# Bean_revE.net
KiCad netlist of a schematic drawn in EAGLE
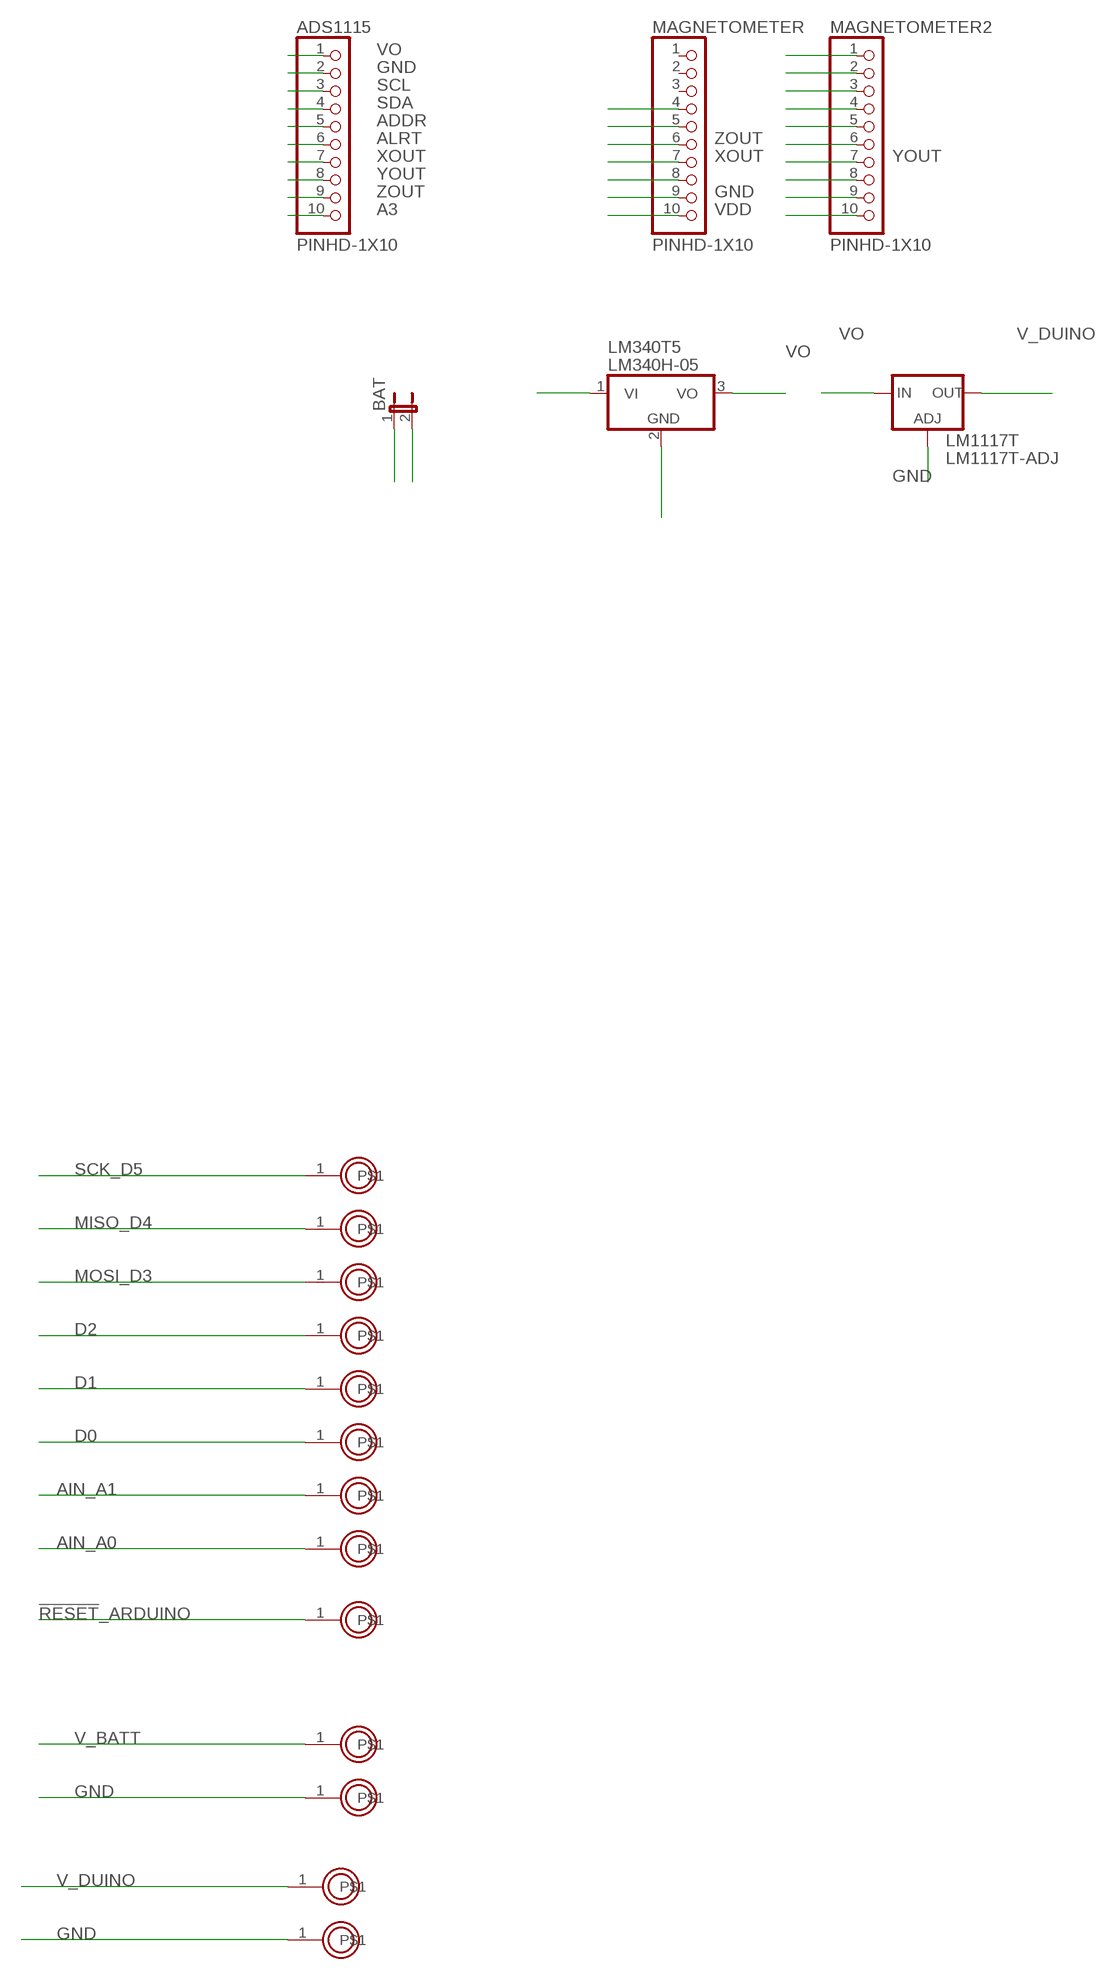
[diagram p0: schematic, sheet 1]

(export (version "E")
  (design (tool "Eeschema 10.0.6"))
  (components
    (comp (ref "ADS1115")
      (value "PINHD-1X10")
      (footprint "eagle-import:1X10-BIG")
      (libsource (lib "eagle-import") (part "PINHD-1X10"))
    )
    (comp (ref "BAT")
      (value "JP1E")
      (footprint "eagle-import:JP1")
      (libsource (lib "eagle-import") (part "JP1E"))
    )
    (comp (ref "LM340T5")
      (value "LM340H-05")
      (footprint "eagle-import:TO220H")
      (libsource (lib "eagle-import") (part "LM340?-H05"))
    )
    (comp (ref "LM1117T")
      (value "LM1117T-ADJ")
      (footprint "eagle-import:TO220")
      (libsource (lib "eagle-import") (part "LM1117T-ADJ"))
    )
    (comp (ref "MAGNETOMETER")
      (value "PINHD-1X10")
      (footprint "eagle-import:1X10-BIG")
      (libsource (lib "eagle-import") (part "PINHD-1X10"))
    )
    (comp (ref "MAGNETOMETER2")
      (value "PINHD-1X10")
      (footprint "eagle-import:1X10-BIG")
      (libsource (lib "eagle-import") (part "PINHD-1X10"))
    )
    (comp (ref "U$1")
      (value "PROTO_POINT")
      (footprint "eagle-import:1X01")
      (libsource (lib "eagle-import") (part "PROTO_POINT"))
    )
    (comp (ref "U$3")
      (value "PROTO_POINT")
      (footprint "eagle-import:1X01")
      (libsource (lib "eagle-import") (part "PROTO_POINT"))
    )
    (comp (ref "U$4")
      (value "PROTO_POINT")
      (footprint "eagle-import:1X01")
      (libsource (lib "eagle-import") (part "PROTO_POINT"))
    )
    (comp (ref "U$5")
      (value "PROTO_POINT")
      (footprint "eagle-import:1X01")
      (libsource (lib "eagle-import") (part "PROTO_POINT"))
    )
    (comp (ref "U$6")
      (value "PROTO_POINT")
      (footprint "eagle-import:1X01")
      (libsource (lib "eagle-import") (part "PROTO_POINT"))
    )
    (comp (ref "U$7")
      (value "PROTO_POINT")
      (footprint "eagle-import:1X01")
      (libsource (lib "eagle-import") (part "PROTO_POINT"))
    )
    (comp (ref "U$8")
      (value "PROTO_POINT")
      (footprint "eagle-import:1X01")
      (libsource (lib "eagle-import") (part "PROTO_POINT"))
    )
    (comp (ref "U$9")
      (value "PROTO_POINT")
      (footprint "eagle-import:1X01")
      (libsource (lib "eagle-import") (part "PROTO_POINT"))
    )
    (comp (ref "U$10")
      (value "PROTO_POINT")
      (footprint "eagle-import:1X01")
      (libsource (lib "eagle-import") (part "PROTO_POINT"))
    )
    (comp (ref "U$45")
      (value "PROTO_POINT")
      (footprint "eagle-import:1X01")
      (libsource (lib "eagle-import") (part "PROTO_POINT"))
    )
    (comp (ref "U$46")
      (value "PROTO_POINT")
      (footprint "eagle-import:1X01")
      (libsource (lib "eagle-import") (part "PROTO_POINT"))
    )
    (comp (ref "U$52")
      (value "PROTO_POINT")
      (footprint "eagle-import:1X01")
      (libsource (lib "eagle-import") (part "PROTO_POINT"))
    )
    (comp (ref "U$53")
      (value "PROTO_POINT")
      (footprint "eagle-import:1X01")
      (libsource (lib "eagle-import") (part "PROTO_POINT"))
    )
  )
  (nets
    (net (code "1") (name "/A3") (class "Default")
      (node (ref "ADS1115") (pin "10") (pinfunction "10_10") (pintype "passive"))
    )
    (net (code "2") (name "/ADDR") (class "Default")
      (node (ref "ADS1115") (pin "5") (pinfunction "5_5") (pintype "passive"))
    )
    (net (code "3") (name "/AIN_A0") (class "Default")
      (node (ref "U$10") (pin "1") (pinfunction "P$1_1") (pintype "bidirectional"))
    )
    (net (code "4") (name "/AIN_A1") (class "Default")
      (node (ref "U$9") (pin "1") (pinfunction "P$1_1") (pintype "bidirectional"))
    )
    (net (code "5") (name "/ALRT") (class "Default")
      (node (ref "ADS1115") (pin "6") (pinfunction "6_6") (pintype "passive"))
    )
    (net (code "6") (name "/D0") (class "Default")
      (node (ref "U$8") (pin "1") (pinfunction "P$1_1") (pintype "bidirectional"))
    )
    (net (code "7") (name "/D1") (class "Default")
      (node (ref "U$7") (pin "1") (pinfunction "P$1_1") (pintype "bidirectional"))
    )
    (net (code "8") (name "/D2") (class "Default")
      (node (ref "U$6") (pin "1") (pinfunction "P$1_1") (pintype "bidirectional"))
    )
    (net (code "9") (name "/GND") (class "Default")
      (node (ref "ADS1115") (pin "2") (pinfunction "2_2") (pintype "passive"))
      (node (ref "BAT") (pin "2") (pinfunction "2_2") (pintype "passive"))
      (node (ref "LM1117T") (pin "1") (pinfunction "ADJ_1") (pintype "input"))
      (node (ref "LM340T5") (pin "2") (pinfunction "GND_2") (pintype "passive"))
      (node (ref "MAGNETOMETER") (pin "9") (pinfunction "9_9") (pintype "passive"))
      (node (ref "U$45") (pin "1") (pinfunction "P$1_1") (pintype "bidirectional"))
      (node (ref "U$53") (pin "1") (pinfunction "P$1_1") (pintype "bidirectional"))
    )
    (net (code "10") (name "/MISO_D4") (class "Default")
      (node (ref "U$4") (pin "1") (pinfunction "P$1_1") (pintype "bidirectional"))
    )
    (net (code "11") (name "/MOSI_D3") (class "Default")
      (node (ref "U$5") (pin "1") (pinfunction "P$1_1") (pintype "bidirectional"))
    )
    (net (code "12") (name "/SCK_D5") (class "Default")
      (node (ref "U$3") (pin "1") (pinfunction "P$1_1") (pintype "bidirectional"))
    )
    (net (code "13") (name "/SCL") (class "Default")
      (node (ref "ADS1115") (pin "3") (pinfunction "3_3") (pintype "passive"))
    )
    (net (code "14") (name "/SDA") (class "Default")
      (node (ref "ADS1115") (pin "4") (pinfunction "4_4") (pintype "passive"))
    )
    (net (code "15") (name "/VDD") (class "Default")
      (node (ref "MAGNETOMETER") (pin "10") (pinfunction "10_10") (pintype "passive"))
    )
    (net (code "16") (name "/VI") (class "Default")
      (node (ref "BAT") (pin "1") (pinfunction "1_1") (pintype "passive"))
      (node (ref "LM340T5") (pin "1") (pinfunction "VI_1") (pintype "input"))
    )
    (net (code "17") (name "/VO") (class "Default")
      (node (ref "ADS1115") (pin "1") (pinfunction "1_1") (pintype "passive"))
      (node (ref "LM1117T") (pin "3") (pinfunction "IN_3") (pintype "input"))
      (node (ref "LM340T5") (pin "3") (pinfunction "VO_3") (pintype "passive"))
    )
    (net (code "18") (name "/V_BATT") (class "Default")
      (node (ref "U$52") (pin "1") (pinfunction "P$1_1") (pintype "bidirectional"))
    )
    (net (code "19") (name "/V_DUINO") (class "Default")
      (node (ref "LM1117T") (pin "2") (pinfunction "OUT_2") (pintype "passive"))
      (node (ref "U$1") (pin "1") (pinfunction "P$1_1") (pintype "bidirectional"))
    )
    (net (code "20") (name "/XOUT") (class "Default")
      (node (ref "ADS1115") (pin "7") (pinfunction "7_7") (pintype "passive"))
      (node (ref "MAGNETOMETER") (pin "7") (pinfunction "7_7") (pintype "passive"))
    )
    (net (code "21") (name "/YOUT") (class "Default")
      (node (ref "ADS1115") (pin "8") (pinfunction "8_8") (pintype "passive"))
      (node (ref "MAGNETOMETER2") (pin "7") (pinfunction "7_7") (pintype "passive"))
    )
    (net (code "22") (name "/ZOUT") (class "Default")
      (node (ref "ADS1115") (pin "9") (pinfunction "9_9") (pintype "passive"))
      (node (ref "MAGNETOMETER") (pin "6") (pinfunction "6_6") (pintype "passive"))
    )
    (net (code "23") (name "/~{RESET}_ARDUINO") (class "Default")
      (node (ref "U$46") (pin "1") (pinfunction "P$1_1") (pintype "bidirectional"))
    )
    (net (code "24") (name "unconnected-(MAGNETOMETER-Pad1)") (class "Default")
      (node (ref "MAGNETOMETER") (pin "1") (pinfunction "1_1") (pintype "passive"))
    )
    (net (code "25") (name "unconnected-(MAGNETOMETER-Pad2)") (class "Default")
      (node (ref "MAGNETOMETER") (pin "2") (pinfunction "2_2") (pintype "passive"))
    )
    (net (code "26") (name "unconnected-(MAGNETOMETER-Pad3)") (class "Default")
      (node (ref "MAGNETOMETER") (pin "3") (pinfunction "3_3") (pintype "passive"))
    )
    (net (code "27") (name "unconnected-(MAGNETOMETER-Pad4)") (class "Default")
      (node (ref "MAGNETOMETER") (pin "4") (pinfunction "4_4") (pintype "passive"))
    )
    (net (code "28") (name "unconnected-(MAGNETOMETER-Pad5)") (class "Default")
      (node (ref "MAGNETOMETER") (pin "5") (pinfunction "5_5") (pintype "passive"))
    )
    (net (code "29") (name "unconnected-(MAGNETOMETER-Pad8)") (class "Default")
      (node (ref "MAGNETOMETER") (pin "8") (pinfunction "8_8") (pintype "passive"))
    )
    (net (code "30") (name "unconnected-(MAGNETOMETER2-Pad1)") (class "Default")
      (node (ref "MAGNETOMETER2") (pin "1") (pinfunction "1_1") (pintype "passive"))
    )
    (net (code "31") (name "unconnected-(MAGNETOMETER2-Pad2)") (class "Default")
      (node (ref "MAGNETOMETER2") (pin "2") (pinfunction "2_2") (pintype "passive"))
    )
    (net (code "32") (name "unconnected-(MAGNETOMETER2-Pad3)") (class "Default")
      (node (ref "MAGNETOMETER2") (pin "3") (pinfunction "3_3") (pintype "passive"))
    )
    (net (code "33") (name "unconnected-(MAGNETOMETER2-Pad4)") (class "Default")
      (node (ref "MAGNETOMETER2") (pin "4") (pinfunction "4_4") (pintype "passive"))
    )
    (net (code "34") (name "unconnected-(MAGNETOMETER2-Pad5)") (class "Default")
      (node (ref "MAGNETOMETER2") (pin "5") (pinfunction "5_5") (pintype "passive"))
    )
    (net (code "35") (name "unconnected-(MAGNETOMETER2-Pad6)") (class "Default")
      (node (ref "MAGNETOMETER2") (pin "6") (pinfunction "6_6") (pintype "passive"))
    )
    (net (code "36") (name "unconnected-(MAGNETOMETER2-Pad8)") (class "Default")
      (node (ref "MAGNETOMETER2") (pin "8") (pinfunction "8_8") (pintype "passive"))
    )
    (net (code "37") (name "unconnected-(MAGNETOMETER2-Pad9)") (class "Default")
      (node (ref "MAGNETOMETER2") (pin "9") (pinfunction "9_9") (pintype "passive"))
    )
    (net (code "38") (name "unconnected-(MAGNETOMETER2-Pad10)") (class "Default")
      (node (ref "MAGNETOMETER2") (pin "10") (pinfunction "10_10") (pintype "passive"))
    )
  )
)
